# AD936X.net
KiCad netlist of a schematic drawn in Altium Designer
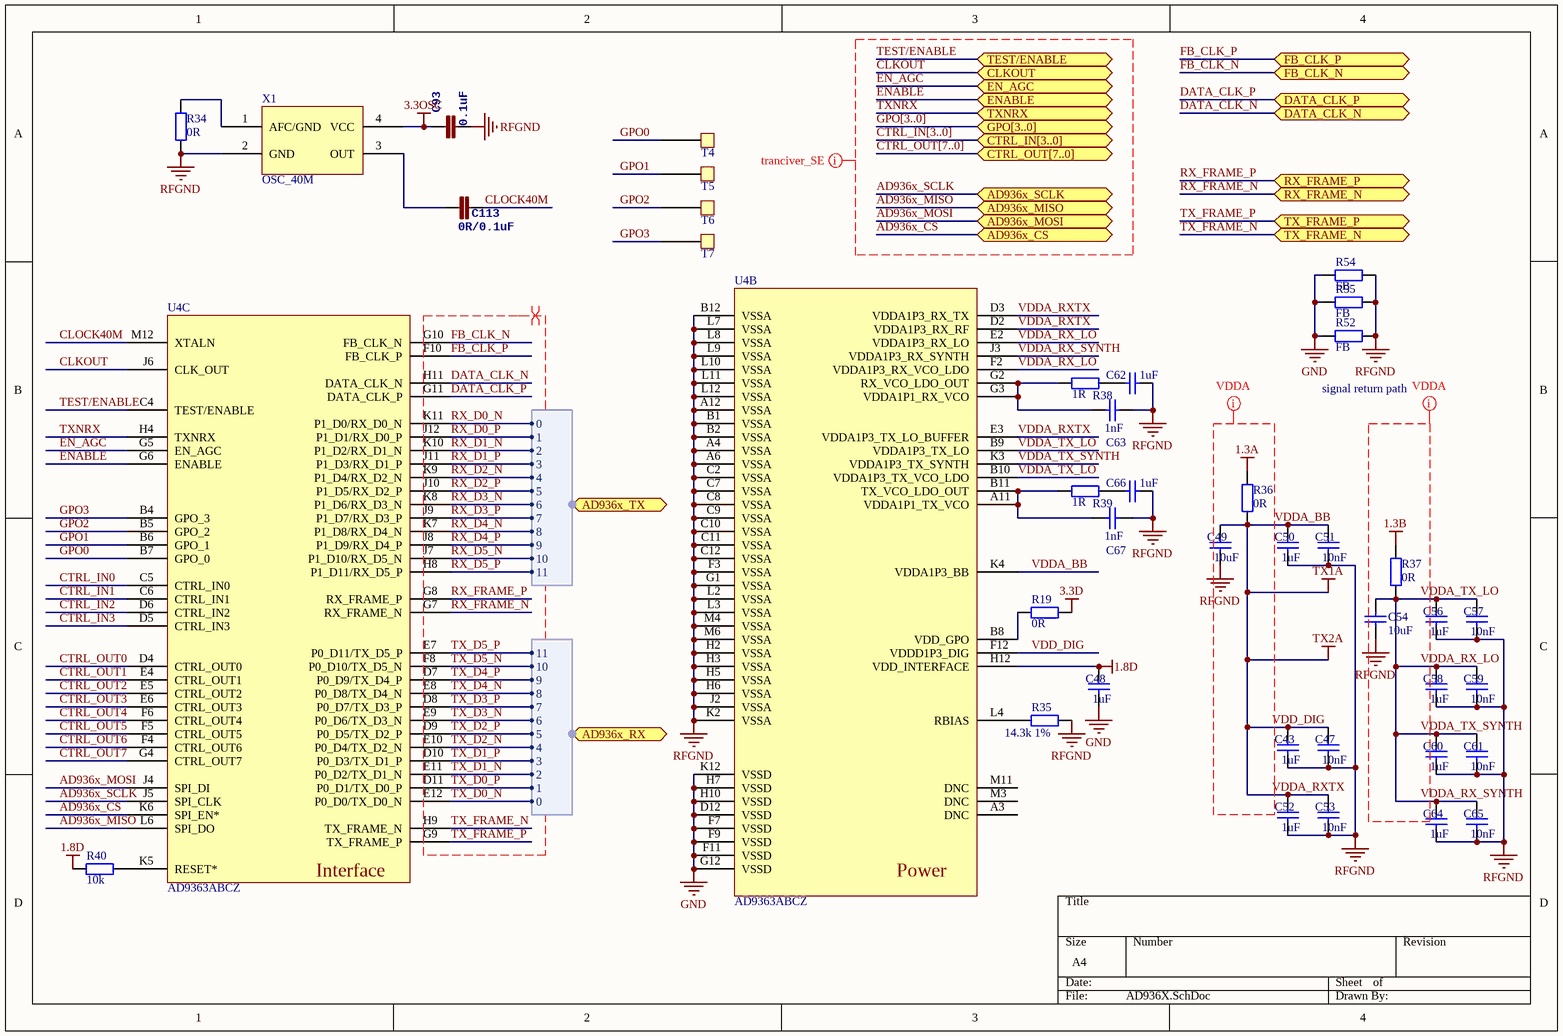
[diagram p0: AD936X.SchDoc]

(export (version "E")
  (design (tool "Eeschema 10.0.6"))
  (components
    (comp (ref "C43")
      (value "1uF")
      (footprint "0402")
      (description "Capacitor")
      (fields (field (name "PUBLISHER") "Altium Limited"))
      (libsource (lib "RTC6705") (part "Cap"))
    )
    (comp (ref "C47")
      (value "10nF")
      (footprint "0402")
      (description "Capacitor")
      (fields (field (name "PUBLISHER") "Altium Limited"))
      (libsource (lib "RTC6705") (part "Cap"))
    )
    (comp (ref "C48")
      (value "1uF")
      (footprint "0402")
      (description "Capacitor")
      (fields (field (name "PUBLISHER") "Altium Limited"))
      (libsource (lib "RTC6705") (part "Cap"))
    )
    (comp (ref "C49")
      (value "10uF")
      (footprint "0805")
      (description "Capacitor")
      (fields (field (name "PUBLISHER") "Altium Limited"))
      (libsource (lib "RTC6705") (part "Cap"))
    )
    (comp (ref "C50")
      (value "1uF")
      (footprint "0402")
      (description "Capacitor")
      (fields (field (name "PUBLISHER") "Altium Limited"))
      (libsource (lib "RTC6705") (part "Cap"))
    )
    (comp (ref "C51")
      (value "10nF")
      (footprint "0402")
      (description "Capacitor")
      (fields (field (name "PUBLISHER") "Altium Limited"))
      (libsource (lib "RTC6705") (part "Cap"))
    )
    (comp (ref "C52")
      (value "1uF")
      (footprint "0402")
      (description "Capacitor")
      (fields (field (name "PUBLISHER") "Altium Limited"))
      (libsource (lib "RTC6705") (part "Cap"))
    )
    (comp (ref "C53")
      (value "10nF")
      (footprint "0402")
      (description "Capacitor")
      (fields (field (name "PUBLISHER") "Altium Limited"))
      (libsource (lib "RTC6705") (part "Cap"))
    )
    (comp (ref "C54")
      (value "10uF")
      (footprint "0805")
      (description "Capacitor")
      (fields (field (name "PUBLISHER") "Altium Limited"))
      (libsource (lib "RTC6705") (part "Cap"))
    )
    (comp (ref "C56")
      (value "1uF")
      (footprint "0402")
      (description "Capacitor")
      (fields (field (name "PUBLISHER") "Altium Limited"))
      (libsource (lib "RTC6705") (part "Cap"))
    )
    (comp (ref "C57")
      (value "10nF")
      (footprint "0402")
      (description "Capacitor")
      (fields (field (name "PUBLISHER") "Altium Limited"))
      (libsource (lib "RTC6705") (part "Cap"))
    )
    (comp (ref "C58")
      (value "1uF")
      (footprint "0402")
      (description "Capacitor")
      (fields (field (name "PUBLISHER") "Altium Limited"))
      (libsource (lib "RTC6705") (part "Cap"))
    )
    (comp (ref "C59")
      (value "10nF")
      (footprint "0402")
      (description "Capacitor")
      (fields (field (name "PUBLISHER") "Altium Limited"))
      (libsource (lib "RTC6705") (part "Cap"))
    )
    (comp (ref "C60")
      (value "1uF")
      (footprint "0402")
      (description "Capacitor")
      (fields (field (name "PUBLISHER") "Altium Limited"))
      (libsource (lib "RTC6705") (part "Cap"))
    )
    (comp (ref "C61")
      (value "10nF")
      (footprint "0402")
      (description "Capacitor")
      (fields (field (name "PUBLISHER") "Altium Limited"))
      (libsource (lib "RTC6705") (part "Cap"))
    )
    (comp (ref "C62")
      (value "1uF")
      (footprint "0402")
      (description "Capacitor")
      (fields (field (name "PUBLISHER") "Altium Limited"))
      (libsource (lib "RTC6705") (part "Cap"))
    )
    (comp (ref "C63")
      (value "1nF")
      (footprint "0402")
      (description "Capacitor")
      (fields (field (name "PUBLISHER") "Altium Limited"))
      (libsource (lib "RTC6705") (part "Cap"))
    )
    (comp (ref "C64")
      (value "1uF")
      (footprint "0402")
      (description "Capacitor")
      (fields (field (name "PUBLISHER") "Altium Limited"))
      (libsource (lib "RTC6705") (part "Cap"))
    )
    (comp (ref "C65")
      (value "10nF")
      (footprint "0402")
      (description "Capacitor")
      (fields (field (name "PUBLISHER") "Altium Limited"))
      (libsource (lib "RTC6705") (part "Cap"))
    )
    (comp (ref "C66")
      (value "1uF")
      (footprint "0402")
      (description "Capacitor")
      (fields (field (name "PUBLISHER") "Altium Limited"))
      (libsource (lib "RTC6705") (part "Cap"))
    )
    (comp (ref "C67")
      (value "1nF")
      (footprint "0402")
      (description "Capacitor")
      (fields (field (name "PUBLISHER") "Altium Limited"))
      (libsource (lib "RTC6705") (part "Cap"))
    )
    (comp (ref "C93")
      (value "0.1uF")
      (footprint "0402")
      (description "<b>Capacitor</b>\nStandard 0603 ceramic capacitor, and 0.1\" leaded capacitor.")
      (fields (field (name "PARTNO") "CC0402ZRY5V7BB104"))
      (libsource (lib "pixhawk2") (part "CAP0402-CAP"))
    )
    (comp (ref "C113")
      (value "0R/0.1uF")
      (footprint "0402")
      (description "<b>Capacitor</b>\nStandard 0603 ceramic capacitor, and 0.1\" leaded capacitor.")
      (fields (field (name "PARTNO") "CC0402ZRY5V7BB104"))
      (libsource (lib "pixhawk2") (part "CAP0402-CAP"))
    )
    (comp (ref "R19")
      (value "0R")
      (footprint "0402")
      (description "Resistor")
      (fields (field (name "PUBLISHER") "Altium Limited"))
      (libsource (lib "") (part "Res2_2"))
    )
    (comp (ref "R34")
      (value "0R")
      (footprint "0402")
      (description "Resistor")
      (fields (field (name "PUBLISHER") "Altium Limited"))
      (libsource (lib "") (part "Res2_1"))
    )
    (comp (ref "R35")
      (value "14.3k 1%")
      (footprint "0603")
      (description "Resistor")
      (fields (field (name "PUBLISHER") "Altium Limited"))
      (libsource (lib "") (part "Res2_2"))
    )
    (comp (ref "R36")
      (value "0R")
      (footprint "0603")
      (description "Resistor")
      (fields (field (name "PUBLISHER") "Altium Limited"))
      (libsource (lib "") (part "Res2_1"))
    )
    (comp (ref "R37")
      (value "0R")
      (footprint "0603")
      (description "Resistor")
      (fields (field (name "PUBLISHER") "Altium Limited"))
      (libsource (lib "") (part "Res2_1"))
    )
    (comp (ref "R38")
      (value "1R")
      (footprint "0402")
      (description "Resistor")
      (fields (field (name "PUBLISHER") "Altium Limited"))
      (libsource (lib "Miscellaneous Devices") (part "Res2"))
    )
    (comp (ref "R39")
      (value "1R")
      (footprint "0402")
      (description "Resistor")
      (fields (field (name "PUBLISHER") "Altium Limited"))
      (libsource (lib "Miscellaneous Devices") (part "Res2"))
    )
    (comp (ref "R40")
      (value "10k")
      (footprint "0402")
      (description "Resistor")
      (fields (field (name "PUBLISHER") "Altium Limited"))
      (libsource (lib "Miscellaneous Devices") (part "Res2"))
    )
    (comp (ref "R52")
      (value "FB")
      (footprint "0402")
      (description "Resistor")
      (fields (field (name "PUBLISHER") "Altium Limited"))
      (libsource (lib "Miscellaneous Devices") (part "Res2"))
    )
    (comp (ref "R54")
      (value "FB")
      (footprint "0402")
      (description "Resistor")
      (fields (field (name "PUBLISHER") "Altium Limited"))
      (libsource (lib "Miscellaneous Devices") (part "Res2"))
    )
    (comp (ref "R55")
      (value "FB")
      (footprint "0402")
      (description "Resistor")
      (fields (field (name "PUBLISHER") "Altium Limited"))
      (libsource (lib "Miscellaneous Devices") (part "Res2"))
    )
    (comp (ref "T4") (value "TestPad") (footprint "TestPad - 1mm") (libsource (lib "sch") (part "TestPad")))
    (comp (ref "T5") (value "TestPad") (footprint "TestPad - 1mm") (libsource (lib "sch") (part "TestPad")))
    (comp (ref "T6") (value "TestPad") (footprint "TestPad - 1mm") (libsource (lib "sch") (part "TestPad")))
    (comp (ref "T7") (value "TestPad") (footprint "TestPad - 1mm") (libsource (lib "sch") (part "TestPad")))
    (comp (ref "U4")
      (value "AD9363ABCZ")
      (footprint "AD936X")
      (description "Imported")
      (libsource (lib "AD936X") (part "AD9363ABCZ"))
    )
    (comp (ref "X1") (value "OSC_40M") (footprint "TXC_7Q") (libsource (lib "F4SDR") (part "OSC_40M")))
  )
  (nets
    (net (code "2") (name "/AD936x_CS") (class "Default")
      (node (ref "U4") (pin "K6") (pinfunction "SPI_EN*_K6") (pintype "passive"))
    )
    (net (code "3") (name "/AD936x_MISO") (class "Default")
      (node (ref "U4") (pin "L6") (pinfunction "SPI_DO_L6") (pintype "passive"))
    )
    (net (code "4") (name "/AD936x_MOSI") (class "Default")
      (node (ref "U4") (pin "J4") (pinfunction "SPI_DI_J4") (pintype "passive"))
    )
    (net (code "5") (name "/AD936x_SCLK") (class "Default")
      (node (ref "U4") (pin "J5") (pinfunction "SPI_CLK_J5") (pintype "passive"))
    )
    (net (code "6") (name "/CLKOUT") (class "Default")
      (node (ref "U4") (pin "J6") (pinfunction "CLK_OUT_J6") (pintype "passive"))
    )
    (net (code "7") (name "/CLOCK40M") (class "Default")
      (node (ref "C113") (pin "2") (pinfunction "2_2") (pintype "passive"))
      (node (ref "U4") (pin "M12") (pinfunction "XTALN_M12") (pintype "passive"))
    )
    (net (code "8") (name "/CTRL_IN0") (class "Default")
      (node (ref "U4") (pin "C5") (pinfunction "CTRL_IN0_C5") (pintype "passive"))
    )
    (net (code "9") (name "/CTRL_IN1") (class "Default")
      (node (ref "U4") (pin "C6") (pinfunction "CTRL_IN1_C6") (pintype "passive"))
    )
    (net (code "10") (name "/CTRL_IN2") (class "Default")
      (node (ref "U4") (pin "D6") (pinfunction "CTRL_IN2_D6") (pintype "passive"))
    )
    (net (code "11") (name "/CTRL_IN3") (class "Default")
      (node (ref "U4") (pin "D5") (pinfunction "CTRL_IN3_D5") (pintype "passive"))
    )
    (net (code "13") (name "/CTRL_OUT0") (class "Default")
      (node (ref "U4") (pin "D4") (pinfunction "CTRL_OUT0_D4") (pintype "passive"))
    )
    (net (code "14") (name "/CTRL_OUT1") (class "Default")
      (node (ref "U4") (pin "E4") (pinfunction "CTRL_OUT1_E4") (pintype "passive"))
    )
    (net (code "15") (name "/CTRL_OUT2") (class "Default")
      (node (ref "U4") (pin "E5") (pinfunction "CTRL_OUT2_E5") (pintype "passive"))
    )
    (net (code "16") (name "/CTRL_OUT3") (class "Default")
      (node (ref "U4") (pin "E6") (pinfunction "CTRL_OUT3_E6") (pintype "passive"))
    )
    (net (code "17") (name "/CTRL_OUT4") (class "Default")
      (node (ref "U4") (pin "F6") (pinfunction "CTRL_OUT4_F6") (pintype "passive"))
    )
    (net (code "18") (name "/CTRL_OUT5") (class "Default")
      (node (ref "U4") (pin "F5") (pinfunction "CTRL_OUT5_F5") (pintype "passive"))
    )
    (net (code "19") (name "/CTRL_OUT6") (class "Default")
      (node (ref "U4") (pin "F4") (pinfunction "CTRL_OUT6_F4") (pintype "passive"))
    )
    (net (code "20") (name "/CTRL_OUT7") (class "Default")
      (node (ref "U4") (pin "G4") (pinfunction "CTRL_OUT7_G4") (pintype "passive"))
    )
    (net (code "22") (name "/DATA_CLK_N") (class "Default")
      (node (ref "U4") (pin "H11") (pinfunction "DATA_CLK_N_H11") (pintype "passive"))
    )
    (net (code "23") (name "/DATA_CLK_P") (class "Default")
      (node (ref "U4") (pin "G11") (pinfunction "DATA_CLK_P_G11") (pintype "passive"))
    )
    (net (code "24") (name "/ENABLE") (class "Default")
      (node (ref "U4") (pin "G6") (pinfunction "ENABLE_G6") (pintype "passive"))
    )
    (net (code "25") (name "/EN_AGC") (class "Default")
      (node (ref "U4") (pin "G5") (pinfunction "EN_AGC_G5") (pintype "passive"))
    )
    (net (code "26") (name "/FB_CLK_N") (class "Default")
      (node (ref "U4") (pin "G10") (pinfunction "FB_CLK_N_G10") (pintype "passive"))
    )
    (net (code "27") (name "/FB_CLK_P") (class "Default")
      (node (ref "U4") (pin "F10") (pinfunction "FB_CLK_P_F10") (pintype "passive"))
    )
    (net (code "28") (name "/GPO0") (class "Default")
      (node (ref "T4") (pin "1") (pinfunction "3_1") (pintype "passive"))
      (node (ref "U4") (pin "B7") (pinfunction "GPO_0_B7") (pintype "passive"))
    )
    (net (code "29") (name "/GPO1") (class "Default")
      (node (ref "T5") (pin "1") (pinfunction "3_1") (pintype "passive"))
      (node (ref "U4") (pin "B6") (pinfunction "GPO_1_B6") (pintype "passive"))
    )
    (net (code "30") (name "/GPO2") (class "Default")
      (node (ref "T6") (pin "1") (pinfunction "3_1") (pintype "passive"))
      (node (ref "U4") (pin "B5") (pinfunction "GPO_2_B5") (pintype "passive"))
    )
    (net (code "31") (name "/GPO3") (class "Default")
      (node (ref "T7") (pin "1") (pinfunction "3_1") (pintype "passive"))
      (node (ref "U4") (pin "B4") (pinfunction "GPO_3_B4") (pintype "passive"))
    )
    (net (code "33") (name "/RX_D0_N") (class "Default")
      (node (ref "U4") (pin "K11") (pinfunction "P1_D0/RX_D0_N_K11") (pintype "passive"))
    )
    (net (code "34") (name "/RX_D0_P") (class "Default")
      (node (ref "U4") (pin "J12") (pinfunction "P1_D1/RX_D0_P_J12") (pintype "passive"))
    )
    (net (code "35") (name "/RX_D1_N") (class "Default")
      (node (ref "U4") (pin "K10") (pinfunction "P1_D2/RX_D1_N_K10") (pintype "passive"))
    )
    (net (code "36") (name "/RX_D1_P") (class "Default")
      (node (ref "U4") (pin "J11") (pinfunction "P1_D3/RX_D1_P_J11") (pintype "passive"))
    )
    (net (code "37") (name "/RX_D2_N") (class "Default")
      (node (ref "U4") (pin "K9") (pinfunction "P1_D4/RX_D2_N_K9") (pintype "passive"))
    )
    (net (code "38") (name "/RX_D2_P") (class "Default")
      (node (ref "U4") (pin "J10") (pinfunction "P1_D5/RX_D2_P_J10") (pintype "passive"))
    )
    (net (code "39") (name "/RX_D3_N") (class "Default")
      (node (ref "U4") (pin "K8") (pinfunction "P1_D6/RX_D3_N_K8") (pintype "passive"))
    )
    (net (code "40") (name "/RX_D3_P") (class "Default")
      (node (ref "U4") (pin "J9") (pinfunction "P1_D7/RX_D3_P_J9") (pintype "passive"))
    )
    (net (code "41") (name "/RX_D4_N") (class "Default")
      (node (ref "U4") (pin "K7") (pinfunction "P1_D8/RX_D4_N_K7") (pintype "passive"))
    )
    (net (code "42") (name "/RX_D4_P") (class "Default")
      (node (ref "U4") (pin "J8") (pinfunction "P1_D9/RX_D4_P_J8") (pintype "passive"))
    )
    (net (code "43") (name "/RX_D5_N") (class "Default")
      (node (ref "U4") (pin "J7") (pinfunction "P1_D10/RX_D5_N_J7") (pintype "passive"))
    )
    (net (code "44") (name "/RX_D5_P") (class "Default")
      (node (ref "U4") (pin "H8") (pinfunction "P1_D11/RX_D5_P_H8") (pintype "passive"))
    )
    (net (code "45") (name "/RX_FRAME_N") (class "Default")
      (node (ref "U4") (pin "G7") (pinfunction "RX_FRAME_N_G7") (pintype "passive"))
    )
    (net (code "46") (name "/RX_FRAME_P") (class "Default")
      (node (ref "U4") (pin "G8") (pinfunction "RX_FRAME_P_G8") (pintype "passive"))
    )
    (net (code "47") (name "/TEST{slash}ENABLE") (class "Default")
      (node (ref "U4") (pin "C4") (pinfunction "TEST/ENABLE_C4") (pintype "passive"))
    )
    (net (code "48") (name "/TXNRX") (class "Default")
      (node (ref "U4") (pin "H4") (pinfunction "TXNRX_H4") (pintype "passive"))
    )
    (net (code "49") (name "/TX_D0_N") (class "Default")
      (node (ref "U4") (pin "E12") (pinfunction "P0_D0/TX_D0_N_E12") (pintype "passive"))
    )
    (net (code "50") (name "/TX_D0_P") (class "Default")
      (node (ref "U4") (pin "D11") (pinfunction "P0_D1/TX_D0_P_D11") (pintype "passive"))
    )
    (net (code "51") (name "/TX_D1_N") (class "Default")
      (node (ref "U4") (pin "E11") (pinfunction "P0_D2/TX_D1_N_E11") (pintype "passive"))
    )
    (net (code "52") (name "/TX_D1_P") (class "Default")
      (node (ref "U4") (pin "D10") (pinfunction "P0_D3/TX_D1_P_D10") (pintype "passive"))
    )
    (net (code "53") (name "/TX_D2_N") (class "Default")
      (node (ref "U4") (pin "E10") (pinfunction "P0_D4/TX_D2_N_E10") (pintype "passive"))
    )
    (net (code "54") (name "/TX_D2_P") (class "Default")
      (node (ref "U4") (pin "D9") (pinfunction "P0_D5/TX_D2_P_D9") (pintype "passive"))
    )
    (net (code "55") (name "/TX_D3_N") (class "Default")
      (node (ref "U4") (pin "E9") (pinfunction "P0_D6/TX_D3_N_E9") (pintype "passive"))
    )
    (net (code "56") (name "/TX_D3_P") (class "Default")
      (node (ref "U4") (pin "D8") (pinfunction "P0_D7/TX_D3_P_D8") (pintype "passive"))
    )
    (net (code "57") (name "/TX_D4_N") (class "Default")
      (node (ref "U4") (pin "E8") (pinfunction "P0_D8/TX_D4_N_E8") (pintype "passive"))
    )
    (net (code "58") (name "/TX_D4_P") (class "Default")
      (node (ref "U4") (pin "D7") (pinfunction "P0_D9/TX_D4_P_D7") (pintype "passive"))
    )
    (net (code "59") (name "/TX_D5_N") (class "Default")
      (node (ref "U4") (pin "F8") (pinfunction "P0_D10/TX_D5_N_F8") (pintype "passive"))
    )
    (net (code "60") (name "/TX_D5_P") (class "Default")
      (node (ref "U4") (pin "E7") (pinfunction "P0_D11/TX_D5_P_E7") (pintype "passive"))
    )
    (net (code "61") (name "/TX_FRAME_N") (class "Default")
      (node (ref "U4") (pin "H9") (pinfunction "TX_FRAME_N_H9") (pintype "passive"))
    )
    (net (code "62") (name "/TX_FRAME_P") (class "Default")
      (node (ref "U4") (pin "G9") (pinfunction "TX_FRAME_P_G9") (pintype "passive"))
    )
    (net (code "63") (name "/VDDA_RX_LO") (class "Default")
      (node (ref "C54") (pin "2") (pinfunction "2_2") (pintype "passive"))
      (node (ref "C56") (pin "1") (pinfunction "1_1") (pintype "passive"))
      (node (ref "C57") (pin "1") (pinfunction "1_1") (pintype "passive"))
      (node (ref "C58") (pin "1") (pinfunction "1_1") (pintype "passive"))
      (node (ref "C59") (pin "1") (pinfunction "1_1") (pintype "passive"))
      (node (ref "C60") (pin "1") (pinfunction "1_1") (pintype "passive"))
      (node (ref "C61") (pin "1") (pinfunction "1_1") (pintype "passive"))
      (node (ref "C64") (pin "1") (pinfunction "1_1") (pintype "passive"))
      (node (ref "C65") (pin "1") (pinfunction "1_1") (pintype "passive"))
      (node (ref "R37") (pin "2") (pinfunction "2_2") (pintype "passive"))
      (node (ref "U4") (pin "B10") (pinfunction "VDDA1P3_TX_VCO_LDO_B10") (pintype "passive"))
      (node (ref "U4") (pin "B9") (pinfunction "VDDA1P3_TX_LO_B9") (pintype "passive"))
      (node (ref "U4") (pin "E2") (pinfunction "VDDA1P3_RX_LO_E2") (pintype "passive"))
      (node (ref "U4") (pin "F2") (pinfunction "VDDA1P3_RX_VCO_LDO_F2") (pintype "passive"))
      (node (ref "U4") (pin "J3") (pinfunction "VDDA1P3_RX_SYNTH_J3") (pintype "passive"))
      (node (ref "U4") (pin "K3") (pinfunction "VDDA1P3_TX_SYNTH_K3") (pintype "passive"))
    )
    (net (code "65") (name "1.3A") (class "Default")
      (node (ref "R36") (pin "1") (pinfunction "1_1") (pintype "passive"))
    )
    (net (code "66") (name "1.3B") (class "Default")
      (node (ref "R37") (pin "1") (pinfunction "1_1") (pintype "passive"))
    )
    (net (code "67") (name "1.8D") (class "Default")
      (node (ref "C48") (pin "1") (pinfunction "1_1") (pintype "passive"))
      (node (ref "R40") (pin "2") (pinfunction "2_2") (pintype "passive"))
      (node (ref "U4") (pin "H12") (pinfunction "VDD_INTERFACE_H12") (pintype "passive"))
    )
    (net (code "68") (name "3.3D") (class "Default")
      (node (ref "R19") (pin "2") (pinfunction "2_2") (pintype "passive"))
    )
    (net (code "69") (name "3.3OSC") (class "Default")
      (node (ref "C93") (pin "1") (pinfunction "1_1") (pintype "passive"))
      (node (ref "X1") (pin "4") (pinfunction "VCC_4") (pintype "passive"))
    )
    (net (code "70") (name "GND") (class "Default")
      (node (ref "C48") (pin "2") (pinfunction "2_2") (pintype "passive"))
      (node (ref "R52") (pin "2") (pinfunction "2_2") (pintype "passive"))
      (node (ref "R54") (pin "2") (pinfunction "2_2") (pintype "passive"))
      (node (ref "R55") (pin "2") (pinfunction "2_2") (pintype "passive"))
      (node (ref "U4") (pin "D12") (pinfunction "VSSD_D12") (pintype "passive"))
      (node (ref "U4") (pin "F11") (pinfunction "VSSD_F11") (pintype "passive"))
      (node (ref "U4") (pin "F7") (pinfunction "VSSD_F7") (pintype "passive"))
      (node (ref "U4") (pin "F9") (pinfunction "VSSD_F9") (pintype "passive"))
      (node (ref "U4") (pin "G12") (pinfunction "VSSD_G12") (pintype "passive"))
      (node (ref "U4") (pin "H10") (pinfunction "VSSD_H10") (pintype "passive"))
      (node (ref "U4") (pin "H7") (pinfunction "VSSD_H7") (pintype "passive"))
      (node (ref "U4") (pin "K12") (pinfunction "VSSD_K12") (pintype "passive"))
    )
    (net (code "71") (name "Net-(C62-Pad1)") (class "Default")
      (node (ref "C62") (pin "1") (pinfunction "1_1") (pintype "passive"))
      (node (ref "R38") (pin "1") (pinfunction "1_1") (pintype "passive"))
    )
    (net (code "72") (name "Net-(C66-Pad1)") (class "Default")
      (node (ref "C66") (pin "1") (pinfunction "1_1") (pintype "passive"))
      (node (ref "R39") (pin "1") (pinfunction "1_1") (pintype "passive"))
    )
    (net (code "73") (name "Net-(U4B-RBIAS)") (class "Default")
      (node (ref "R35") (pin "1") (pinfunction "1_1") (pintype "passive"))
      (node (ref "U4") (pin "L4") (pinfunction "RBIAS_L4") (pintype "passive"))
    )
    (net (code "74") (name "Net-(U4B-RX_VCO_LDO_OUT)") (class "Default")
      (node (ref "C63") (pin "1") (pinfunction "1_1") (pintype "passive"))
      (node (ref "R38") (pin "2") (pinfunction "2_2") (pintype "passive"))
      (node (ref "U4") (pin "G2") (pinfunction "RX_VCO_LDO_OUT_G2") (pintype "passive"))
      (node (ref "U4") (pin "G3") (pinfunction "VDDA1P1_RX_VCO_G3") (pintype "passive"))
    )
    (net (code "75") (name "Net-(U4B-TX_VCO_LDO_OUT)") (class "Default")
      (node (ref "C67") (pin "1") (pinfunction "1_1") (pintype "passive"))
      (node (ref "R39") (pin "2") (pinfunction "2_2") (pintype "passive"))
      (node (ref "U4") (pin "A11") (pinfunction "VDDA1P1_TX_VCO_A11") (pintype "passive"))
      (node (ref "U4") (pin "B11") (pinfunction "TX_VCO_LDO_OUT_B11") (pintype "passive"))
    )
    (net (code "76") (name "Net-(U4B-VDD_GPO)") (class "Default")
      (node (ref "R19") (pin "1") (pinfunction "1_1") (pintype "passive"))
      (node (ref "U4") (pin "B8") (pinfunction "VDD_GPO_B8") (pintype "passive"))
    )
    (net (code "77") (name "Net-(U4C-RESET*)") (class "Default")
      (node (ref "R40") (pin "1") (pinfunction "1_1") (pintype "passive"))
      (node (ref "U4") (pin "K5") (pinfunction "RESET*_K5") (pintype "passive"))
    )
    (net (code "78") (name "Net-(X1-AFC{slash}GND)") (class "Default")
      (node (ref "R34") (pin "1") (pinfunction "1_1") (pintype "passive"))
      (node (ref "X1") (pin "1") (pinfunction "AFC/GND_1") (pintype "passive"))
    )
    (net (code "79") (name "Net-(X1-OUT)") (class "Default")
      (node (ref "C113") (pin "1") (pinfunction "1_1") (pintype "passive"))
      (node (ref "X1") (pin "3") (pinfunction "OUT_3") (pintype "passive"))
    )
    (net (code "80") (name "RFGND") (class "Default")
      (node (ref "C43") (pin "2") (pinfunction "2_2") (pintype "passive"))
      (node (ref "C47") (pin "2") (pinfunction "2_2") (pintype "passive"))
      (node (ref "C49") (pin "2") (pinfunction "2_2") (pintype "passive"))
      (node (ref "C50") (pin "2") (pinfunction "2_2") (pintype "passive"))
      (node (ref "C51") (pin "2") (pinfunction "2_2") (pintype "passive"))
      (node (ref "C52") (pin "2") (pinfunction "2_2") (pintype "passive"))
      (node (ref "C53") (pin "2") (pinfunction "2_2") (pintype "passive"))
      (node (ref "C54") (pin "1") (pinfunction "1_1") (pintype "passive"))
      (node (ref "C56") (pin "2") (pinfunction "2_2") (pintype "passive"))
      (node (ref "C57") (pin "2") (pinfunction "2_2") (pintype "passive"))
      (node (ref "C58") (pin "2") (pinfunction "2_2") (pintype "passive"))
      (node (ref "C59") (pin "2") (pinfunction "2_2") (pintype "passive"))
      (node (ref "C60") (pin "2") (pinfunction "2_2") (pintype "passive"))
      (node (ref "C61") (pin "2") (pinfunction "2_2") (pintype "passive"))
      (node (ref "C62") (pin "2") (pinfunction "2_2") (pintype "passive"))
      (node (ref "C63") (pin "2") (pinfunction "2_2") (pintype "passive"))
      (node (ref "C64") (pin "2") (pinfunction "2_2") (pintype "passive"))
      (node (ref "C65") (pin "2") (pinfunction "2_2") (pintype "passive"))
      (node (ref "C66") (pin "2") (pinfunction "2_2") (pintype "passive"))
      (node (ref "C67") (pin "2") (pinfunction "2_2") (pintype "passive"))
      (node (ref "C93") (pin "2") (pinfunction "2_2") (pintype "passive"))
      (node (ref "R34") (pin "2") (pinfunction "2_2") (pintype "passive"))
      (node (ref "R35") (pin "2") (pinfunction "2_2") (pintype "passive"))
      (node (ref "R52") (pin "1") (pinfunction "1_1") (pintype "passive"))
      (node (ref "R54") (pin "1") (pinfunction "1_1") (pintype "passive"))
      (node (ref "R55") (pin "1") (pinfunction "1_1") (pintype "passive"))
      (node (ref "U4") (pin "A12") (pinfunction "VSSA_A12") (pintype "passive"))
      (node (ref "U4") (pin "A4") (pinfunction "VSSA_A4") (pintype "passive"))
      (node (ref "U4") (pin "A6") (pinfunction "VSSA_A6") (pintype "passive"))
      (node (ref "U4") (pin "B1") (pinfunction "VSSA_B1") (pintype "passive"))
      (node (ref "U4") (pin "B12") (pinfunction "VSSA_B12") (pintype "passive"))
      (node (ref "U4") (pin "B2") (pinfunction "VSSA_B2") (pintype "passive"))
      (node (ref "U4") (pin "C10") (pinfunction "VSSA_C10") (pintype "passive"))
      (node (ref "U4") (pin "C11") (pinfunction "VSSA_C11") (pintype "passive"))
      (node (ref "U4") (pin "C12") (pinfunction "VSSA_C12") (pintype "passive"))
      (node (ref "U4") (pin "C2") (pinfunction "VSSA_C2") (pintype "passive"))
      (node (ref "U4") (pin "C7") (pinfunction "VSSA_C7") (pintype "passive"))
      (node (ref "U4") (pin "C8") (pinfunction "VSSA_C8") (pintype "passive"))
      (node (ref "U4") (pin "C9") (pinfunction "VSSA_C9") (pintype "passive"))
      (node (ref "U4") (pin "F3") (pinfunction "VSSA_F3") (pintype "passive"))
      (node (ref "U4") (pin "G1") (pinfunction "VSSA_G1") (pintype "passive"))
      (node (ref "U4") (pin "H2") (pinfunction "VSSA_H2") (pintype "passive"))
      (node (ref "U4") (pin "H3") (pinfunction "VSSA_H3") (pintype "passive"))
      (node (ref "U4") (pin "H5") (pinfunction "VSSA_H5") (pintype "passive"))
      (node (ref "U4") (pin "H6") (pinfunction "VSSA_H6") (pintype "passive"))
      (node (ref "U4") (pin "J2") (pinfunction "VSSA_J2") (pintype "passive"))
      (node (ref "U4") (pin "K2") (pinfunction "VSSA_K2") (pintype "passive"))
      (node (ref "U4") (pin "L10") (pinfunction "VSSA_L10") (pintype "passive"))
      (node (ref "U4") (pin "L11") (pinfunction "VSSA_L11") (pintype "passive"))
      (node (ref "U4") (pin "L12") (pinfunction "VSSA_L12") (pintype "passive"))
      (node (ref "U4") (pin "L2") (pinfunction "VSSA_L2") (pintype "passive"))
      (node (ref "U4") (pin "L3") (pinfunction "VSSA_L3") (pintype "passive"))
      (node (ref "U4") (pin "L7") (pinfunction "VSSA_L7") (pintype "passive"))
      (node (ref "U4") (pin "L8") (pinfunction "VSSA_L8") (pintype "passive"))
      (node (ref "U4") (pin "L9") (pinfunction "VSSA_L9") (pintype "passive"))
      (node (ref "U4") (pin "M4") (pinfunction "VSSA_M4") (pintype "passive"))
      (node (ref "U4") (pin "M6") (pinfunction "VSSA_M6") (pintype "passive"))
      (node (ref "X1") (pin "2") (pinfunction "GND_2") (pintype "passive"))
    )
    (net (code "81") (name "TX1A") (class "Default")
      (node (ref "C43") (pin "1") (pinfunction "1_1") (pintype "passive"))
      (node (ref "C47") (pin "1") (pinfunction "1_1") (pintype "passive"))
      (node (ref "C49") (pin "1") (pinfunction "1_1") (pintype "passive"))
      (node (ref "C50") (pin "1") (pinfunction "1_1") (pintype "passive"))
      (node (ref "C51") (pin "1") (pinfunction "1_1") (pintype "passive"))
      (node (ref "C52") (pin "1") (pinfunction "1_1") (pintype "passive"))
      (node (ref "C53") (pin "1") (pinfunction "1_1") (pintype "passive"))
      (node (ref "R36") (pin "2") (pinfunction "2_2") (pintype "passive"))
      (node (ref "U4") (pin "D2") (pinfunction "VDDA1P3_RX_RF_D2") (pintype "passive"))
      (node (ref "U4") (pin "D3") (pinfunction "VDDA1P3_RX_TX_D3") (pintype "passive"))
      (node (ref "U4") (pin "E3") (pinfunction "VDDA1P3_TX_LO_BUFFER_E3") (pintype "passive"))
      (node (ref "U4") (pin "F12") (pinfunction "VDDD1P3_DIG_F12") (pintype "passive"))
      (node (ref "U4") (pin "K4") (pinfunction "VDDA1P3_BB_K4") (pintype "passive"))
    )
    (net (code "82") (name "unconnected-(U4B-DNC-PadA3)") (class "Default")
      (node (ref "U4") (pin "A3") (pinfunction "DNC_A3") (pintype "passive"))
    )
    (net (code "83") (name "unconnected-(U4B-DNC-PadM3)") (class "Default")
      (node (ref "U4") (pin "M3") (pinfunction "DNC_M3") (pintype "passive"))
    )
    (net (code "84") (name "unconnected-(U4B-DNC-PadM11)") (class "Default")
      (node (ref "U4") (pin "M11") (pinfunction "DNC_M11") (pintype "passive"))
    )
  )
)
